# power.net
KiCad netlist of a schematic drawn in Altium Designer
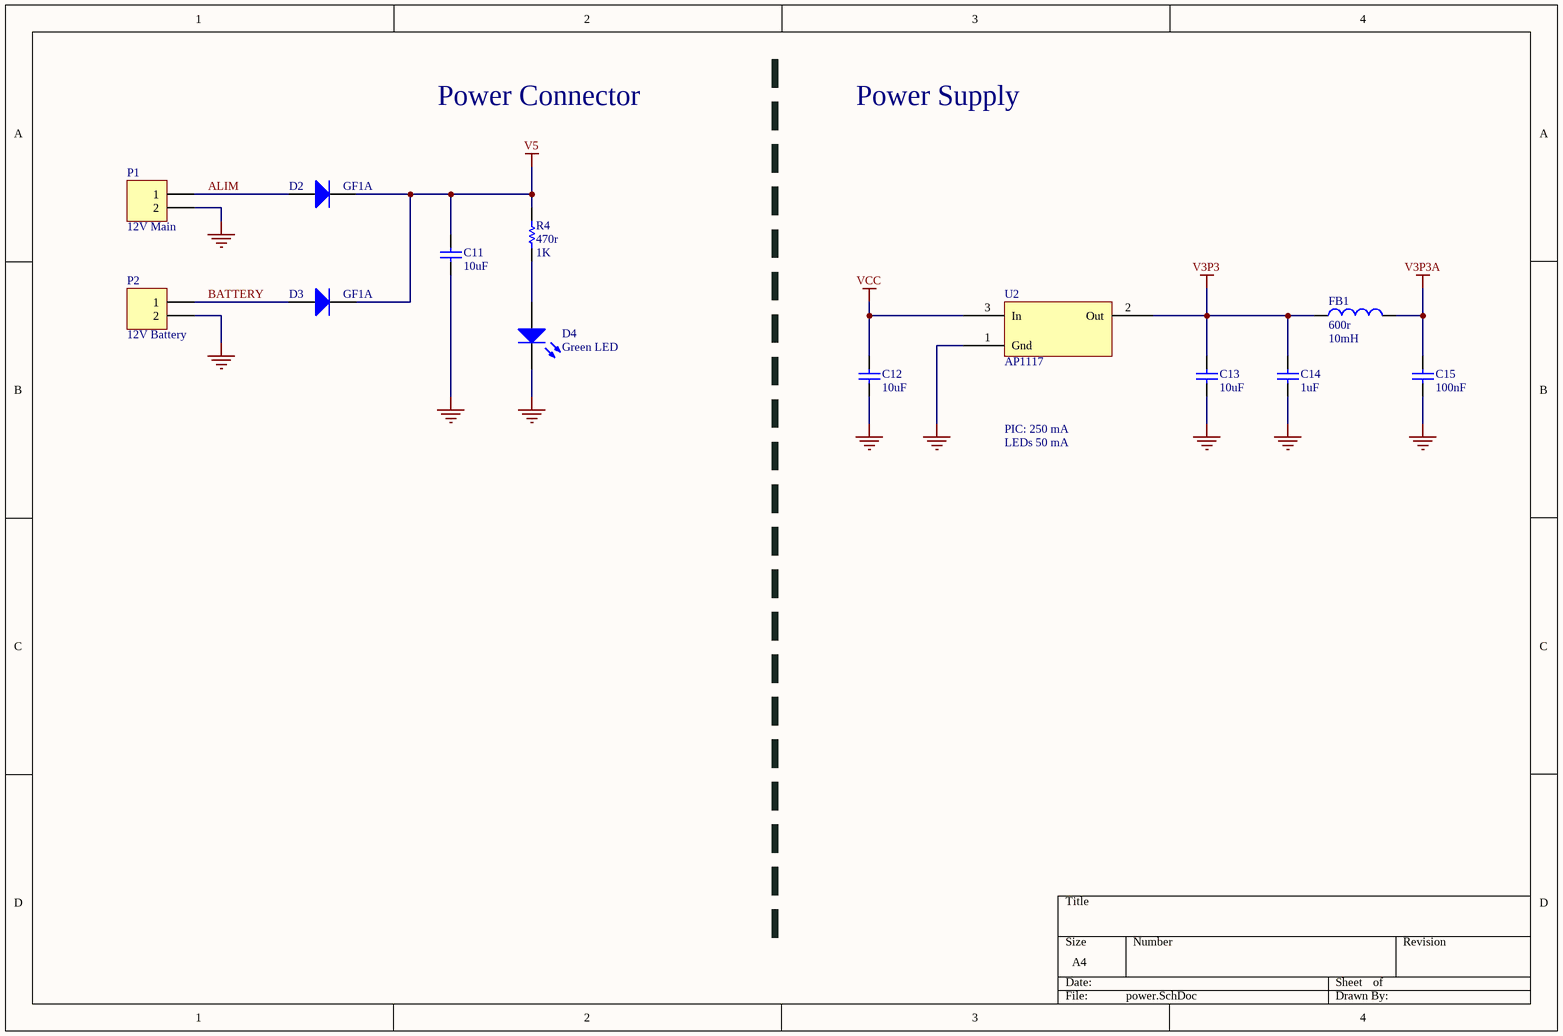
[diagram p0: power.SchDoc]

(export (version "E")
  (design (tool "Eeschema 10.0.6"))
  (components
    (comp (ref "C11")
      (value "10uF")
      (footprint "2012/0805")
      (fields (field (name "PUBLISHER") "Altium Limited"))
      (libsource (lib "TP3_lib") (part "Capacitor"))
    )
    (comp (ref "C12")
      (value "10uF")
      (footprint "2012/0805")
      (description "Capacitor")
      (fields (field (name "PUBLISHER") "Altium Limited"))
      (libsource (lib "TP3_lib") (part "Capacitor"))
    )
    (comp (ref "C13")
      (value "10uF")
      (footprint "2012/0805")
      (description "Capacitor")
      (fields (field (name "PUBLISHER") "Altium Limited"))
      (libsource (lib "TP3_lib") (part "Capacitor"))
    )
    (comp (ref "C14")
      (value "1uF")
      (footprint "2012/0805")
      (description "Capacitor")
      (fields (field (name "PUBLISHER") "Altium Limited"))
      (libsource (lib "TP3_lib") (part "Capacitor"))
    )
    (comp (ref "C15")
      (value "100nF")
      (footprint "2012/0805")
      (description "Capacitor")
      (fields (field (name "PUBLISHER") "Altium Limited"))
      (libsource (lib "TP3_lib") (part "Capacitor"))
    )
    (comp (ref "D2")
      (value "GF1A")
      (footprint "SMA/DO-214AC_21")
      (description "Diode")
      (fields (field (name "PUBLISHER") "Altium Limited"))
      (libsource (lib "TP3_lib") (part "Diode"))
    )
    (comp (ref "D3")
      (value "GF1A")
      (footprint "SMA/DO-214AC_21")
      (description "Diode")
      (fields (field (name "PUBLISHER") "Altium Limited"))
      (libsource (lib "TP3_lib") (part "Diode"))
    )
    (comp (ref "D4")
      (value "Green LED")
      (footprint "2012/0805")
      (description "LED")
      (fields (field (name "PUBLISHER") "Altium Limited"))
      (libsource (lib "TP3_lib") (part "LED"))
    )
    (comp (ref "FB1")
      (value "600r")
      (footprint "INDC1608AN")
      (description "Inductor")
      (fields (field (name "ALTIUM_VALUE") "10mH") (field (name "PUBLISHER") "Altium Limited"))
      (libsource (lib "TP3_lib") (part "Inductor"))
    )
    (comp (ref "P1")
      (value "12V Main")
      (footprint "PHOENIX_1985195")
      (description "Header, 2-Pin")
      (fields (field (name "PUBLISHER") "Altium Limited"))
      (libsource (lib "TP3_lib") (part "Header 2"))
    )
    (comp (ref "P2")
      (value "12V Battery")
      (footprint "PHOENIX_1985195")
      (description "Header, 2-Pin")
      (fields (field (name "PUBLISHER") "Altium Limited"))
      (libsource (lib "TP3_lib") (part "Header 2"))
    )
    (comp (ref "R4")
      (value "470r")
      (footprint "1608/0603")
      (description "Resistor")
      (fields (field (name "ALTIUM_VALUE") "1K") (field (name "PUBLISHER") "Altium Limited"))
      (libsource (lib "TP3_lib") (part "Resistor"))
    )
    (comp (ref "U2")
      (value "AP1117")
      (footprint "AP1117")
      (description "Voltage Regulator")
      (libsource (lib "TP3_lib") (part "AP1117"))
    )
  )
  (nets
    (net (code "1") (name "/ALIM") (class "Default")
      (node (ref "D2") (pin "1") (pinfunction "A_1") (pintype "passive"))
      (node (ref "P1") (pin "1") (pinfunction "1_1") (pintype "passive"))
    )
    (net (code "2") (name "/BATTERY") (class "Default")
      (node (ref "D3") (pin "1") (pinfunction "A_1") (pintype "passive"))
      (node (ref "P2") (pin "1") (pinfunction "1_1") (pintype "passive"))
    )
    (net (code "3") (name "GND") (class "Default")
      (node (ref "C11") (pin "1") (pinfunction "1_1") (pintype "passive"))
      (node (ref "C12") (pin "1") (pinfunction "1_1") (pintype "passive"))
      (node (ref "C13") (pin "1") (pinfunction "1_1") (pintype "passive"))
      (node (ref "C14") (pin "1") (pinfunction "1_1") (pintype "passive"))
      (node (ref "C15") (pin "1") (pinfunction "1_1") (pintype "passive"))
      (node (ref "D4") (pin "2") (pinfunction "K_2") (pintype "passive"))
      (node (ref "P1") (pin "2") (pinfunction "2_2") (pintype "passive"))
      (node (ref "P2") (pin "2") (pinfunction "2_2") (pintype "passive"))
      (node (ref "U2") (pin "1") (pinfunction "Gnd_1") (pintype "passive"))
    )
    (net (code "4") (name "Net-(D4-A)") (class "Default")
      (node (ref "D4") (pin "1") (pinfunction "A_1") (pintype "passive"))
      (node (ref "R4") (pin "1") (pinfunction "1_1") (pintype "passive"))
    )
    (net (code "5") (name "V3P3") (class "Default")
      (node (ref "C13") (pin "2") (pinfunction "2_2") (pintype "passive"))
      (node (ref "C14") (pin "2") (pinfunction "2_2") (pintype "passive"))
      (node (ref "FB1") (pin "1") (pinfunction "1_1") (pintype "passive"))
      (node (ref "U2") (pin "2") (pinfunction "Out_2") (pintype "passive"))
    )
    (net (code "6") (name "V3P3A") (class "Default")
      (node (ref "C15") (pin "2") (pinfunction "2_2") (pintype "passive"))
      (node (ref "FB1") (pin "2") (pinfunction "2_2") (pintype "passive"))
    )
    (net (code "7") (name "V5") (class "Default")
      (node (ref "C11") (pin "2") (pinfunction "2_2") (pintype "passive"))
      (node (ref "D2") (pin "2") (pinfunction "K_2") (pintype "passive"))
      (node (ref "D3") (pin "2") (pinfunction "K_2") (pintype "passive"))
      (node (ref "R4") (pin "2") (pinfunction "2_2") (pintype "passive"))
    )
    (net (code "8") (name "VCC") (class "Default")
      (node (ref "C12") (pin "2") (pinfunction "2_2") (pintype "passive"))
      (node (ref "U2") (pin "3") (pinfunction "In_3") (pintype "passive"))
    )
  )
)
